# GPS_Schematic.net
KiCad netlist of a schematic drawn in Altium Designer
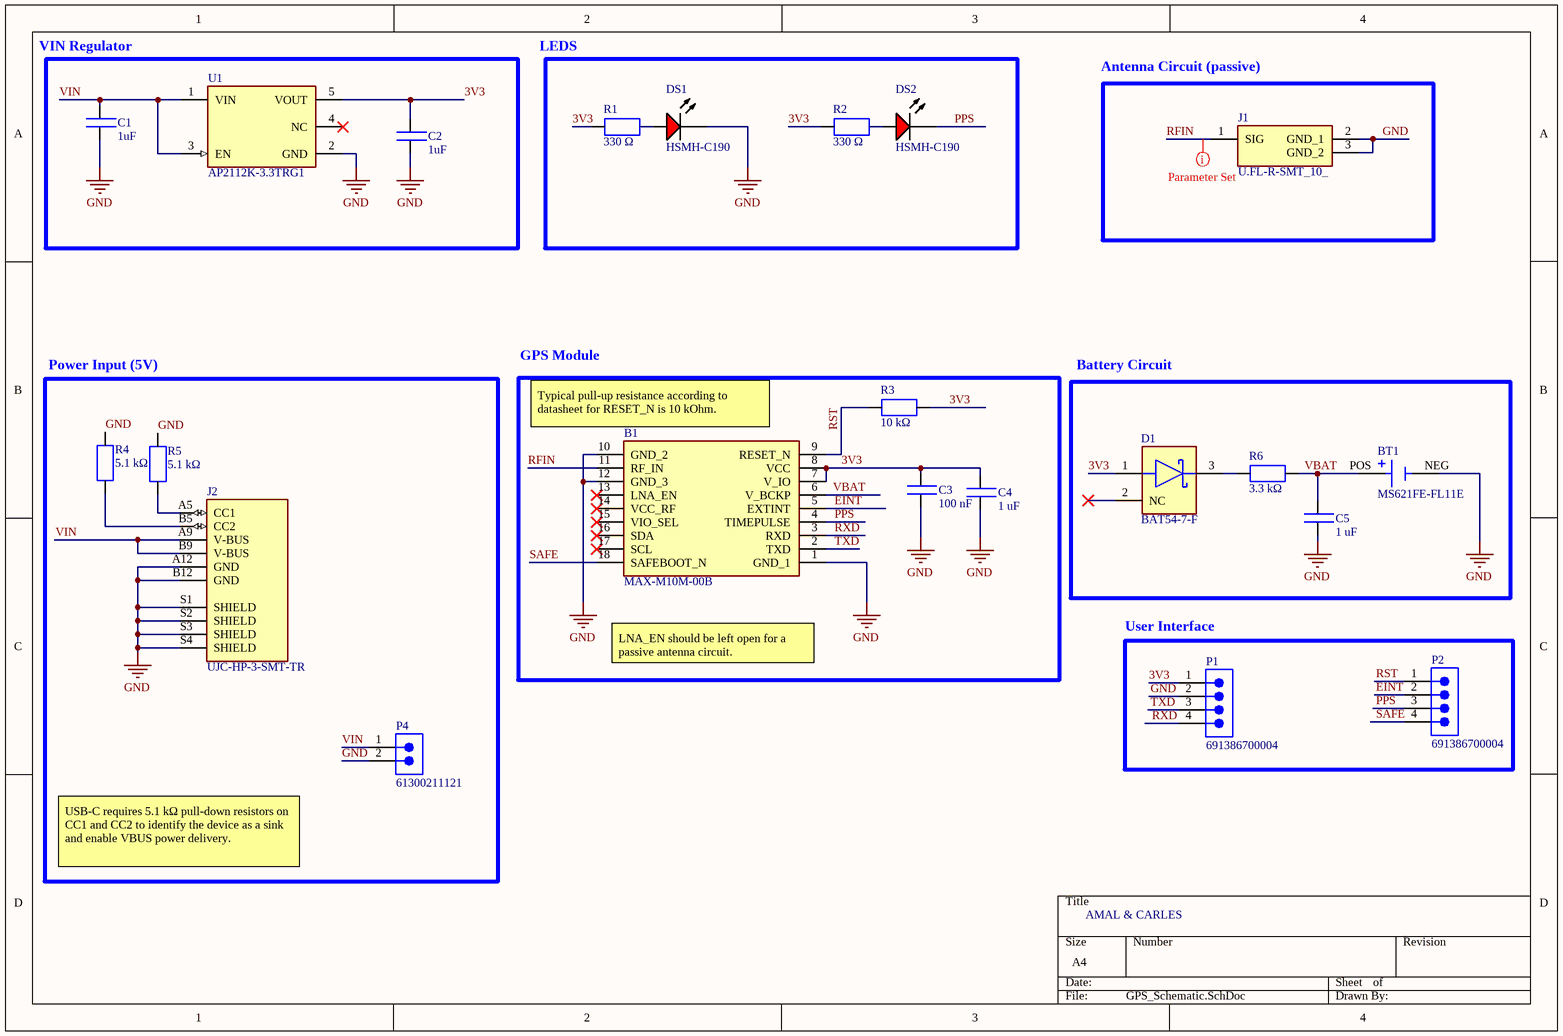
[diagram p0: GPS_Schematic.SchDoc]

(export (version "E")
  (design (tool "Eeschema 10.0.6"))
  (components
    (comp (ref "B1")
      (value "MAX-M10M-00B")
      (footprint "MAXM10M00B")
      (description "GPS Modules u-blox M10 GNSS LCC module, firmware in ROM, crystal oscillator")
      (fields (field (name "MOUSER PART NUMBER") "377-MAX-M10M-00B"))
      (libsource (lib "Generic-Schematic-Library") (part "MAX-M10M-00B"))
    )
    (comp (ref "BT1")
      (value "MS621FE-FL11E")
      (footprint "BAT_MS621FE-FL11E")
      (description "Coin, 6.8mm 3 V Lithium Battery Rechargeable (Secondary) 5.5mAh")
      (fields (field (name "MF") "Seiko Instruments"))
      (libsource (lib "Generic-Schematic-Library") (part "MS621FE-FL11E"))
    )
    (comp (ref "C1")
      (value "1uF")
      (footprint "CAP_0402")
      (description "Capacitor SMD 0402 Generic")
      (fields
        (field (name "MANUFACTURER") "YAGEO")
        (field (name "MANUFACTURER PART NUMBER") "CC0402JRNPO9BN101")
      )
      (libsource (lib "Generic-Schematic-Library") (part "CAP_0402"))
    )
    (comp (ref "C2")
      (value "1uF")
      (footprint "CAP_0402")
      (description "Capacitor SMD 0402 Generic")
      (fields
        (field (name "MANUFACTURER") "YAGEO")
        (field (name "MANUFACTURER PART NUMBER") "CC0402JRNPO9BN101")
      )
      (libsource (lib "Generic-Schematic-Library") (part "CAP_0402"))
    )
    (comp (ref "C3")
      (value "100 nF")
      (footprint "CAP_0402")
      (description "Capacitor SMD 0402 Generic")
      (fields
        (field (name "MANUFACTURER") "YAGEO")
        (field (name "MANUFACTURER PART NUMBER") "CC0402JRNPO9BN101")
      )
      (libsource (lib "Generic-Schematic-Library") (part "CAP_0402"))
    )
    (comp (ref "C4")
      (value "1 uF")
      (footprint "CAP_0402")
      (description "Capacitor SMD 0402 Generic")
      (fields
        (field (name "MANUFACTURER") "YAGEO")
        (field (name "MANUFACTURER PART NUMBER") "CC0402JRNPO9BN101")
      )
      (libsource (lib "Generic-Schematic-Library") (part "CAP_0402"))
    )
    (comp (ref "C5")
      (value "1 uF")
      (footprint "CAP_0402")
      (description "Capacitor SMD 0402 Generic")
      (fields
        (field (name "MANUFACTURER") "YAGEO")
        (field (name "MANUFACTURER PART NUMBER") "CC0402JRNPO9BN101")
      )
      (libsource (lib "Generic-Schematic-Library") (part "CAP_0402"))
    )
    (comp (ref "D1")
      (value "BAT54-7-F")
      (footprint "FP-SOT23-IPC_C")
      (description "DIODE SCHOTTKY 30V 200MA SOT23-3")
      (fields
        (field (name "MANUFACTURER") "Diodes Inc.")
        (field (name "OCTOPART") "https://octopart.com/bat54-7-f-diodes+inc.-39681803")
      )
      (libsource (lib "Generic-Schematic-Library") (part "CMP-0303-00002-2"))
    )
    (comp (ref "DS1")
      (value "HSMH-C190")
      (footprint "HSMH-C190")
      (description "LED Uni-Color Red, 65 mW, 20 mA, -40 to 85 degC, 2-Pin SMD, RoHS, Tape and Reel")
      (libsource (lib "Generic-Schematic-Library") (part "HSMH-C190"))
    )
    (comp (ref "DS2")
      (value "HSMH-C190")
      (footprint "HSMH-C190")
      (description "LED Uni-Color Red, 65 mW, 20 mA, -40 to 85 degC, 2-Pin SMD, RoHS, Tape and Reel")
      (libsource (lib "Generic-Schematic-Library") (part "HSMH-C190"))
    )
    (comp (ref "J1")
      (value "U.FL-R-SMT_10_")
      (footprint "UFLRSMT10")
      (description "U.FL (UMCC) Connector Receptacle, Male Pin 50 Ohms Surface Mount Solder")
      (fields
        (field (name "MANUFACTURER_PART_NUMBER") "U.FL-R-SMT(10)")
        (field (name "MOUSER PART NUMBER") "798-U.FL-R-SMT10")
      )
      (libsource (lib "Generic-Schematic-Library") (part "U.FL-R-SMT_10_"))
    )
    (comp (ref "J2")
      (value "UJC-HP-3-SMT-TR")
      (footprint "CUI_UJC-HP-3-SMT-TR")
      (libsource (lib "Generic-Schematic-Library") (part "UJC-HP-3-SMT-TR"))
    )
    (comp (ref "P1")
      (value "691386700004")
      (footprint "CMP-1502-02092-3")
      (description "Terminal Block, 5.00MM, Male Pcb Horizontal/vertical Cab Divisible, 4 Pins")
      (fields (field (name "VOLTAGE") "300V"))
      (libsource (lib "Generic-Schematic-Library") (part "CMP-1502-02092-3"))
    )
    (comp (ref "P2")
      (value "691386700004")
      (footprint "CMP-1502-02092-3")
      (description "Terminal Block, 5.00MM, Male Pcb Horizontal/vertical Cab Divisible, 4 Pins")
      (fields (field (name "VOLTAGE") "300V"))
      (libsource (lib "Generic-Schematic-Library") (part "CMP-1502-02092-3"))
    )
    (comp (ref "P4")
      (value "61300211121")
      (footprint "61300211121")
      (description "THT Vertical Pin Header WR-PHD, Pitch 2.54 mm, Single Row, 2 pins")
      (libsource (lib "Generic-Schematic-Library") (part "CMP-1712-00002-7"))
    )
    (comp (ref "R1")
      (value "330 Ω")
      (footprint "RES_0402")
      (description "Resistor SMD 0402 Generic")
      (fields
        (field (name "MANUFACTURER") "YAGEO")
        (field (name "MANUFACTURER PART NUMBER") "RC0402FR07150KL")
      )
      (libsource (lib "Generic-Schematic-Library") (part "RES_0402"))
    )
    (comp (ref "R2")
      (value "330 Ω")
      (footprint "RES_0402")
      (description "Resistor SMD 0402 Generic")
      (fields
        (field (name "MANUFACTURER") "YAGEO")
        (field (name "MANUFACTURER PART NUMBER") "RC0402FR07150KL")
      )
      (libsource (lib "Generic-Schematic-Library") (part "RES_0402"))
    )
    (comp (ref "R3")
      (value "10 kΩ")
      (footprint "RES_0402")
      (description "Resistor SMD 0402 Generic")
      (fields
        (field (name "MANUFACTURER") "YAGEO")
        (field (name "MANUFACTURER PART NUMBER") "RC0402FR07150KL")
      )
      (libsource (lib "Generic-Schematic-Library") (part "RES_0402"))
    )
    (comp (ref "R4")
      (value "5.1 kΩ")
      (footprint "RES_0402")
      (description "Resistor SMD 0402 Generic")
      (fields
        (field (name "MANUFACTURER") "YAGEO")
        (field (name "MANUFACTURER PART NUMBER") "RC0402FR07150KL")
      )
      (libsource (lib "Generic-Schematic-Library") (part "RES_0402"))
    )
    (comp (ref "R5")
      (value "5.1 kΩ")
      (footprint "RES_0402")
      (description "Resistor SMD 0402 Generic")
      (fields
        (field (name "MANUFACTURER") "YAGEO")
        (field (name "MANUFACTURER PART NUMBER") "RC0402FR07150KL")
      )
      (libsource (lib "Generic-Schematic-Library") (part "RES_0402"))
    )
    (comp (ref "R6")
      (value "3.3 kΩ")
      (footprint "RES_0201")
      (description "Resistor SMD 0201 Generic")
      (fields
        (field (name "MANUFACTURER") "YAGEO")
        (field (name "MANUFACTURER PART NUMBER") "RT0201BRD07200RL")
      )
      (libsource (lib "Generic-Schematic-Library") (part "RES_0201"))
    )
    (comp (ref "U1")
      (value "AP2112K-3.3TRG1")
      (footprint "FP-SOT25-IPC_C")
      (description "IC REG LINEAR 3.3V 600MA SOT25")
      (libsource (lib "Generic-Schematic-Library") (part "CMP-12756-000035-1"))
    )
  )
  (nets
    (net (code "1") (name "/3V3") (class "Default")
      (node (ref "B1") (pin "7") (pinfunction "V_IO_7") (pintype "passive"))
      (node (ref "B1") (pin "8") (pinfunction "VCC_8") (pintype "passive"))
      (node (ref "C2") (pin "2") (pinfunction "2_2") (pintype "passive"))
      (node (ref "C3") (pin "2") (pinfunction "2_2") (pintype "passive"))
      (node (ref "C4") (pin "2") (pinfunction "2_2") (pintype "passive"))
      (node (ref "D1") (pin "1") (pinfunction "A_1") (pintype "passive"))
      (node (ref "P1") (pin "1") (pinfunction "1_1") (pintype "passive"))
      (node (ref "R1") (pin "1") (pinfunction "1_1") (pintype "passive"))
      (node (ref "R2") (pin "1") (pinfunction "1_1") (pintype "passive"))
      (node (ref "R3") (pin "2") (pinfunction "2_2") (pintype "passive"))
      (node (ref "U1") (pin "5") (pinfunction "VOUT_5") (pintype "power_in"))
    )
    (net (code "2") (name "/EINT") (class "Default")
      (node (ref "B1") (pin "5") (pinfunction "EXTINT_5") (pintype "passive"))
      (node (ref "P2") (pin "2") (pinfunction "2_2") (pintype "passive"))
    )
    (net (code "3") (name "/PPS") (class "Default")
      (node (ref "B1") (pin "4") (pinfunction "TIMEPULSE_4") (pintype "passive"))
      (node (ref "DS2") (pin "2") (pinfunction "K_2") (pintype "passive"))
      (node (ref "P2") (pin "3") (pinfunction "3_3") (pintype "passive"))
    )
    (net (code "4") (name "/RFIN") (class "Default")
      (node (ref "B1") (pin "11") (pinfunction "RF_IN_11") (pintype "passive"))
      (node (ref "J1") (pin "1") (pinfunction "SIG_1") (pintype "passive"))
    )
    (net (code "5") (name "/RST") (class "Default")
      (node (ref "B1") (pin "9") (pinfunction "RESET_N_9") (pintype "passive"))
      (node (ref "P2") (pin "1") (pinfunction "1_1") (pintype "passive"))
      (node (ref "R3") (pin "1") (pinfunction "1_1") (pintype "passive"))
    )
    (net (code "6") (name "/RXD") (class "Default")
      (node (ref "B1") (pin "3") (pinfunction "RXD_3") (pintype "passive"))
      (node (ref "P1") (pin "4") (pinfunction "4_4") (pintype "passive"))
    )
    (net (code "7") (name "/SAFE") (class "Default")
      (node (ref "B1") (pin "18") (pinfunction "SAFEBOOT_N_18") (pintype "passive"))
      (node (ref "P2") (pin "4") (pinfunction "4_4") (pintype "passive"))
    )
    (net (code "8") (name "/TXD") (class "Default")
      (node (ref "B1") (pin "2") (pinfunction "TXD_2") (pintype "passive"))
      (node (ref "P1") (pin "3") (pinfunction "3_3") (pintype "passive"))
    )
    (net (code "9") (name "/VBAT") (class "Default")
      (node (ref "B1") (pin "6") (pinfunction "V_BCKP_6") (pintype "passive"))
      (node (ref "BT1") (pin "POS") (pinfunction "POS_POS") (pintype "passive"))
      (node (ref "C5") (pin "2") (pinfunction "2_2") (pintype "passive"))
      (node (ref "R6") (pin "2") (pinfunction "2_2") (pintype "passive"))
    )
    (net (code "10") (name "/VIN") (class "Default")
      (node (ref "C1") (pin "2") (pinfunction "2_2") (pintype "passive"))
      (node (ref "J2") (pin "A9") (pinfunction "V-BUS_A9") (pintype "power_in"))
      (node (ref "J2") (pin "B9") (pinfunction "V-BUS_B9") (pintype "power_in"))
      (node (ref "P4") (pin "1") (pinfunction "1_1") (pintype "passive"))
      (node (ref "U1") (pin "1") (pinfunction "VIN_1") (pintype "power_in"))
      (node (ref "U1") (pin "3") (pinfunction "EN_3") (pintype "input"))
    )
    (net (code "11") (name "GND") (class "Default")
      (node (ref "B1") (pin "1") (pinfunction "GND_1_1") (pintype "passive"))
      (node (ref "B1") (pin "10") (pinfunction "GND_2_10") (pintype "passive"))
      (node (ref "B1") (pin "12") (pinfunction "GND_3_12") (pintype "passive"))
      (node (ref "BT1") (pin "NEG") (pinfunction "NEG_NEG") (pintype "passive"))
      (node (ref "C1") (pin "1") (pinfunction "1_1") (pintype "passive"))
      (node (ref "C2") (pin "1") (pinfunction "1_1") (pintype "passive"))
      (node (ref "C3") (pin "1") (pinfunction "1_1") (pintype "passive"))
      (node (ref "C4") (pin "1") (pinfunction "1_1") (pintype "passive"))
      (node (ref "C5") (pin "1") (pinfunction "1_1") (pintype "passive"))
      (node (ref "DS1") (pin "2") (pinfunction "K_2") (pintype "passive"))
      (node (ref "J1") (pin "2") (pinfunction "GND_1_2") (pintype "passive"))
      (node (ref "J1") (pin "3") (pinfunction "GND_2_3") (pintype "passive"))
      (node (ref "J2") (pin "A12") (pinfunction "GND_A12") (pintype "power_in"))
      (node (ref "J2") (pin "B12") (pinfunction "GND_B12") (pintype "power_in"))
      (node (ref "J2") (pin "S1") (pinfunction "SHIELD_S1") (pintype "passive"))
      (node (ref "J2") (pin "S2") (pinfunction "SHIELD_S2") (pintype "passive"))
      (node (ref "J2") (pin "S3") (pinfunction "SHIELD_S3") (pintype "passive"))
      (node (ref "J2") (pin "S4") (pinfunction "SHIELD_S4") (pintype "passive"))
      (node (ref "P1") (pin "2") (pinfunction "2_2") (pintype "passive"))
      (node (ref "P4") (pin "2") (pinfunction "2_2") (pintype "passive"))
      (node (ref "R4") (pin "1") (pinfunction "1_1") (pintype "passive"))
      (node (ref "R5") (pin "2") (pinfunction "2_2") (pintype "passive"))
      (node (ref "U1") (pin "2") (pinfunction "GND_2") (pintype "power_in"))
    )
    (net (code "12") (name "Net-(D1-C)") (class "Default")
      (node (ref "D1") (pin "3") (pinfunction "C_3") (pintype "passive"))
      (node (ref "R6") (pin "1") (pinfunction "1_1") (pintype "passive"))
    )
    (net (code "13") (name "Net-(DS1-A)") (class "Default")
      (node (ref "DS1") (pin "1") (pinfunction "A_1") (pintype "passive"))
      (node (ref "R1") (pin "2") (pinfunction "2_2") (pintype "passive"))
    )
    (net (code "14") (name "Net-(DS2-A)") (class "Default")
      (node (ref "DS2") (pin "1") (pinfunction "A_1") (pintype "passive"))
      (node (ref "R2") (pin "2") (pinfunction "2_2") (pintype "passive"))
    )
    (net (code "15") (name "Net-(J2-CC1)") (class "Default")
      (node (ref "J2") (pin "A5") (pinfunction "CC1_A5") (pintype "bidirectional"))
      (node (ref "R5") (pin "1") (pinfunction "1_1") (pintype "passive"))
    )
    (net (code "16") (name "Net-(J2-CC2)") (class "Default")
      (node (ref "J2") (pin "B5") (pinfunction "CC2_B5") (pintype "bidirectional"))
      (node (ref "R4") (pin "2") (pinfunction "2_2") (pintype "passive"))
    )
    (net (code "17") (name "unconnected-(B1-LNA_EN-Pad13)") (class "Default")
      (node (ref "B1") (pin "13") (pinfunction "LNA_EN_13") (pintype "passive+no_connect"))
    )
    (net (code "18") (name "unconnected-(B1-SCL-Pad17)") (class "Default")
      (node (ref "B1") (pin "17") (pinfunction "SCL_17") (pintype "passive+no_connect"))
    )
    (net (code "19") (name "unconnected-(B1-SDA-Pad16)") (class "Default")
      (node (ref "B1") (pin "16") (pinfunction "SDA_16") (pintype "passive+no_connect"))
    )
    (net (code "20") (name "unconnected-(B1-VCC_RF-Pad14)") (class "Default")
      (node (ref "B1") (pin "14") (pinfunction "VCC_RF_14") (pintype "passive+no_connect"))
    )
    (net (code "21") (name "unconnected-(B1-VIO_SEL-Pad15)") (class "Default")
      (node (ref "B1") (pin "15") (pinfunction "VIO_SEL_15") (pintype "passive+no_connect"))
    )
    (net (code "22") (name "unconnected-(D1-NC-Pad2)") (class "Default")
      (node (ref "D1") (pin "2") (pinfunction "NC_2") (pintype "passive+no_connect"))
    )
    (net (code "23") (name "unconnected-(U1-NC-Pad4)") (class "Default")
      (node (ref "U1") (pin "4") (pinfunction "NC_4") (pintype "passive+no_connect"))
    )
  )
)
